# MAX86141_HEG_MINI_HEADPIECE.net
KiCad netlist of a schematic drawn in EAGLE
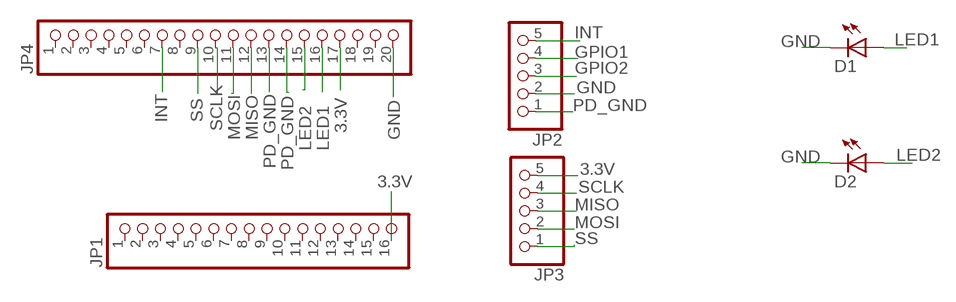
[diagram p0: schematic, sheet 1]

(export (version "E")
  (design (tool "Eeschema 10.0.6"))
  (components
    (comp (ref "D1")
      (value "LED1206")
      (footprint "eagle-import:LED-1206")
      (libsource (lib "eagle-import") (part "LED1206"))
    )
    (comp (ref "D2")
      (value "LED1206")
      (footprint "eagle-import:LED-1206")
      (libsource (lib "eagle-import") (part "LED1206"))
    )
    (comp (ref "JP1")
      (value "PINHD-1X16")
      (footprint "eagle-import:1X16")
      (libsource (lib "eagle-import") (part "PINHD-1X16"))
    )
    (comp (ref "JP2")
      (value "PINHD-1X5")
      (footprint "eagle-import:1X05")
      (libsource (lib "eagle-import") (part "PINHD-1X5"))
    )
    (comp (ref "JP3")
      (value "PINHD-1X5")
      (footprint "eagle-import:1X05")
      (libsource (lib "eagle-import") (part "PINHD-1X5"))
    )
    (comp (ref "JP4")
      (value "PINHD-1X20")
      (footprint "eagle-import:1X20")
      (libsource (lib "eagle-import") (part "PINHD-1X20"))
    )
  )
  (nets
    (net (code "1") (name "/3.3V") (class "Default")
      (node (ref "JP1") (pin "16") (pinfunction "16_16") (pintype "passive"))
      (node (ref "JP3") (pin "5") (pinfunction "5_5") (pintype "passive"))
      (node (ref "JP4") (pin "17") (pinfunction "17_17") (pintype "passive"))
    )
    (net (code "2") (name "/GND") (class "Default")
      (node (ref "D1") (pin "C") (pinfunction "C_C") (pintype "passive"))
      (node (ref "D2") (pin "C") (pinfunction "C_C") (pintype "passive"))
      (node (ref "JP2") (pin "2") (pinfunction "2_2") (pintype "passive"))
      (node (ref "JP4") (pin "20") (pinfunction "20_20") (pintype "passive"))
    )
    (net (code "3") (name "/GPIO1") (class "Default")
      (node (ref "JP2") (pin "4") (pinfunction "4_4") (pintype "passive"))
    )
    (net (code "4") (name "/GPIO2") (class "Default")
      (node (ref "JP2") (pin "3") (pinfunction "3_3") (pintype "passive"))
    )
    (net (code "5") (name "/INT") (class "Default")
      (node (ref "JP2") (pin "5") (pinfunction "5_5") (pintype "passive"))
      (node (ref "JP4") (pin "7") (pinfunction "7_7") (pintype "passive"))
    )
    (net (code "6") (name "/LED1") (class "Default")
      (node (ref "D1") (pin "A") (pinfunction "A_A") (pintype "passive"))
      (node (ref "JP4") (pin "16") (pinfunction "16_16") (pintype "passive"))
    )
    (net (code "7") (name "/LED2") (class "Default")
      (node (ref "D2") (pin "A") (pinfunction "A_A") (pintype "passive"))
      (node (ref "JP4") (pin "15") (pinfunction "15_15") (pintype "passive"))
    )
    (net (code "8") (name "/MISO") (class "Default")
      (node (ref "JP3") (pin "3") (pinfunction "3_3") (pintype "passive"))
      (node (ref "JP4") (pin "12") (pinfunction "12_12") (pintype "passive"))
    )
    (net (code "9") (name "/MOSI") (class "Default")
      (node (ref "JP3") (pin "2") (pinfunction "2_2") (pintype "passive"))
      (node (ref "JP4") (pin "11") (pinfunction "11_11") (pintype "passive"))
    )
    (net (code "10") (name "/PD_GND") (class "Default")
      (node (ref "JP2") (pin "1") (pinfunction "1_1") (pintype "passive"))
      (node (ref "JP4") (pin "13") (pinfunction "13_13") (pintype "passive"))
      (node (ref "JP4") (pin "14") (pinfunction "14_14") (pintype "passive"))
    )
    (net (code "11") (name "/SCLK") (class "Default")
      (node (ref "JP3") (pin "4") (pinfunction "4_4") (pintype "passive"))
      (node (ref "JP4") (pin "10") (pinfunction "10_10") (pintype "passive"))
    )
    (net (code "12") (name "/SS") (class "Default")
      (node (ref "JP3") (pin "1") (pinfunction "1_1") (pintype "passive"))
      (node (ref "JP4") (pin "9") (pinfunction "9_9") (pintype "passive"))
    )
    (net (code "13") (name "unconnected-(JP1-Pad1)") (class "Default")
      (node (ref "JP1") (pin "1") (pinfunction "1_1") (pintype "passive"))
    )
    (net (code "14") (name "unconnected-(JP1-Pad2)") (class "Default")
      (node (ref "JP1") (pin "2") (pinfunction "2_2") (pintype "passive"))
    )
    (net (code "15") (name "unconnected-(JP1-Pad3)") (class "Default")
      (node (ref "JP1") (pin "3") (pinfunction "3_3") (pintype "passive"))
    )
    (net (code "16") (name "unconnected-(JP1-Pad4)") (class "Default")
      (node (ref "JP1") (pin "4") (pinfunction "4_4") (pintype "passive"))
    )
    (net (code "17") (name "unconnected-(JP1-Pad5)") (class "Default")
      (node (ref "JP1") (pin "5") (pinfunction "5_5") (pintype "passive"))
    )
    (net (code "18") (name "unconnected-(JP1-Pad6)") (class "Default")
      (node (ref "JP1") (pin "6") (pinfunction "6_6") (pintype "passive"))
    )
    (net (code "19") (name "unconnected-(JP1-Pad7)") (class "Default")
      (node (ref "JP1") (pin "7") (pinfunction "7_7") (pintype "passive"))
    )
    (net (code "20") (name "unconnected-(JP1-Pad8)") (class "Default")
      (node (ref "JP1") (pin "8") (pinfunction "8_8") (pintype "passive"))
    )
    (net (code "21") (name "unconnected-(JP1-Pad9)") (class "Default")
      (node (ref "JP1") (pin "9") (pinfunction "9_9") (pintype "passive"))
    )
    (net (code "22") (name "unconnected-(JP1-Pad10)") (class "Default")
      (node (ref "JP1") (pin "10") (pinfunction "10_10") (pintype "passive"))
    )
    (net (code "23") (name "unconnected-(JP1-Pad11)") (class "Default")
      (node (ref "JP1") (pin "11") (pinfunction "11_11") (pintype "passive"))
    )
    (net (code "24") (name "unconnected-(JP1-Pad12)") (class "Default")
      (node (ref "JP1") (pin "12") (pinfunction "12_12") (pintype "passive"))
    )
    (net (code "25") (name "unconnected-(JP1-Pad13)") (class "Default")
      (node (ref "JP1") (pin "13") (pinfunction "13_13") (pintype "passive"))
    )
    (net (code "26") (name "unconnected-(JP1-Pad14)") (class "Default")
      (node (ref "JP1") (pin "14") (pinfunction "14_14") (pintype "passive"))
    )
    (net (code "27") (name "unconnected-(JP1-Pad15)") (class "Default")
      (node (ref "JP1") (pin "15") (pinfunction "15_15") (pintype "passive"))
    )
    (net (code "28") (name "unconnected-(JP4-Pad1)") (class "Default")
      (node (ref "JP4") (pin "1") (pinfunction "1_1") (pintype "passive"))
    )
    (net (code "29") (name "unconnected-(JP4-Pad2)") (class "Default")
      (node (ref "JP4") (pin "2") (pinfunction "2_2") (pintype "passive"))
    )
    (net (code "30") (name "unconnected-(JP4-Pad3)") (class "Default")
      (node (ref "JP4") (pin "3") (pinfunction "3_3") (pintype "passive"))
    )
    (net (code "31") (name "unconnected-(JP4-Pad4)") (class "Default")
      (node (ref "JP4") (pin "4") (pinfunction "4_4") (pintype "passive"))
    )
    (net (code "32") (name "unconnected-(JP4-Pad5)") (class "Default")
      (node (ref "JP4") (pin "5") (pinfunction "5_5") (pintype "passive"))
    )
    (net (code "33") (name "unconnected-(JP4-Pad6)") (class "Default")
      (node (ref "JP4") (pin "6") (pinfunction "6_6") (pintype "passive"))
    )
    (net (code "34") (name "unconnected-(JP4-Pad8)") (class "Default")
      (node (ref "JP4") (pin "8") (pinfunction "8_8") (pintype "passive"))
    )
    (net (code "35") (name "unconnected-(JP4-Pad18)") (class "Default")
      (node (ref "JP4") (pin "18") (pinfunction "18_18") (pintype "passive"))
    )
    (net (code "36") (name "unconnected-(JP4-Pad19)") (class "Default")
      (node (ref "JP4") (pin "19") (pinfunction "19_19") (pintype "passive"))
    )
  )
)
